# V-00757-00.net
KiCad netlist of a schematic drawn in EAGLE
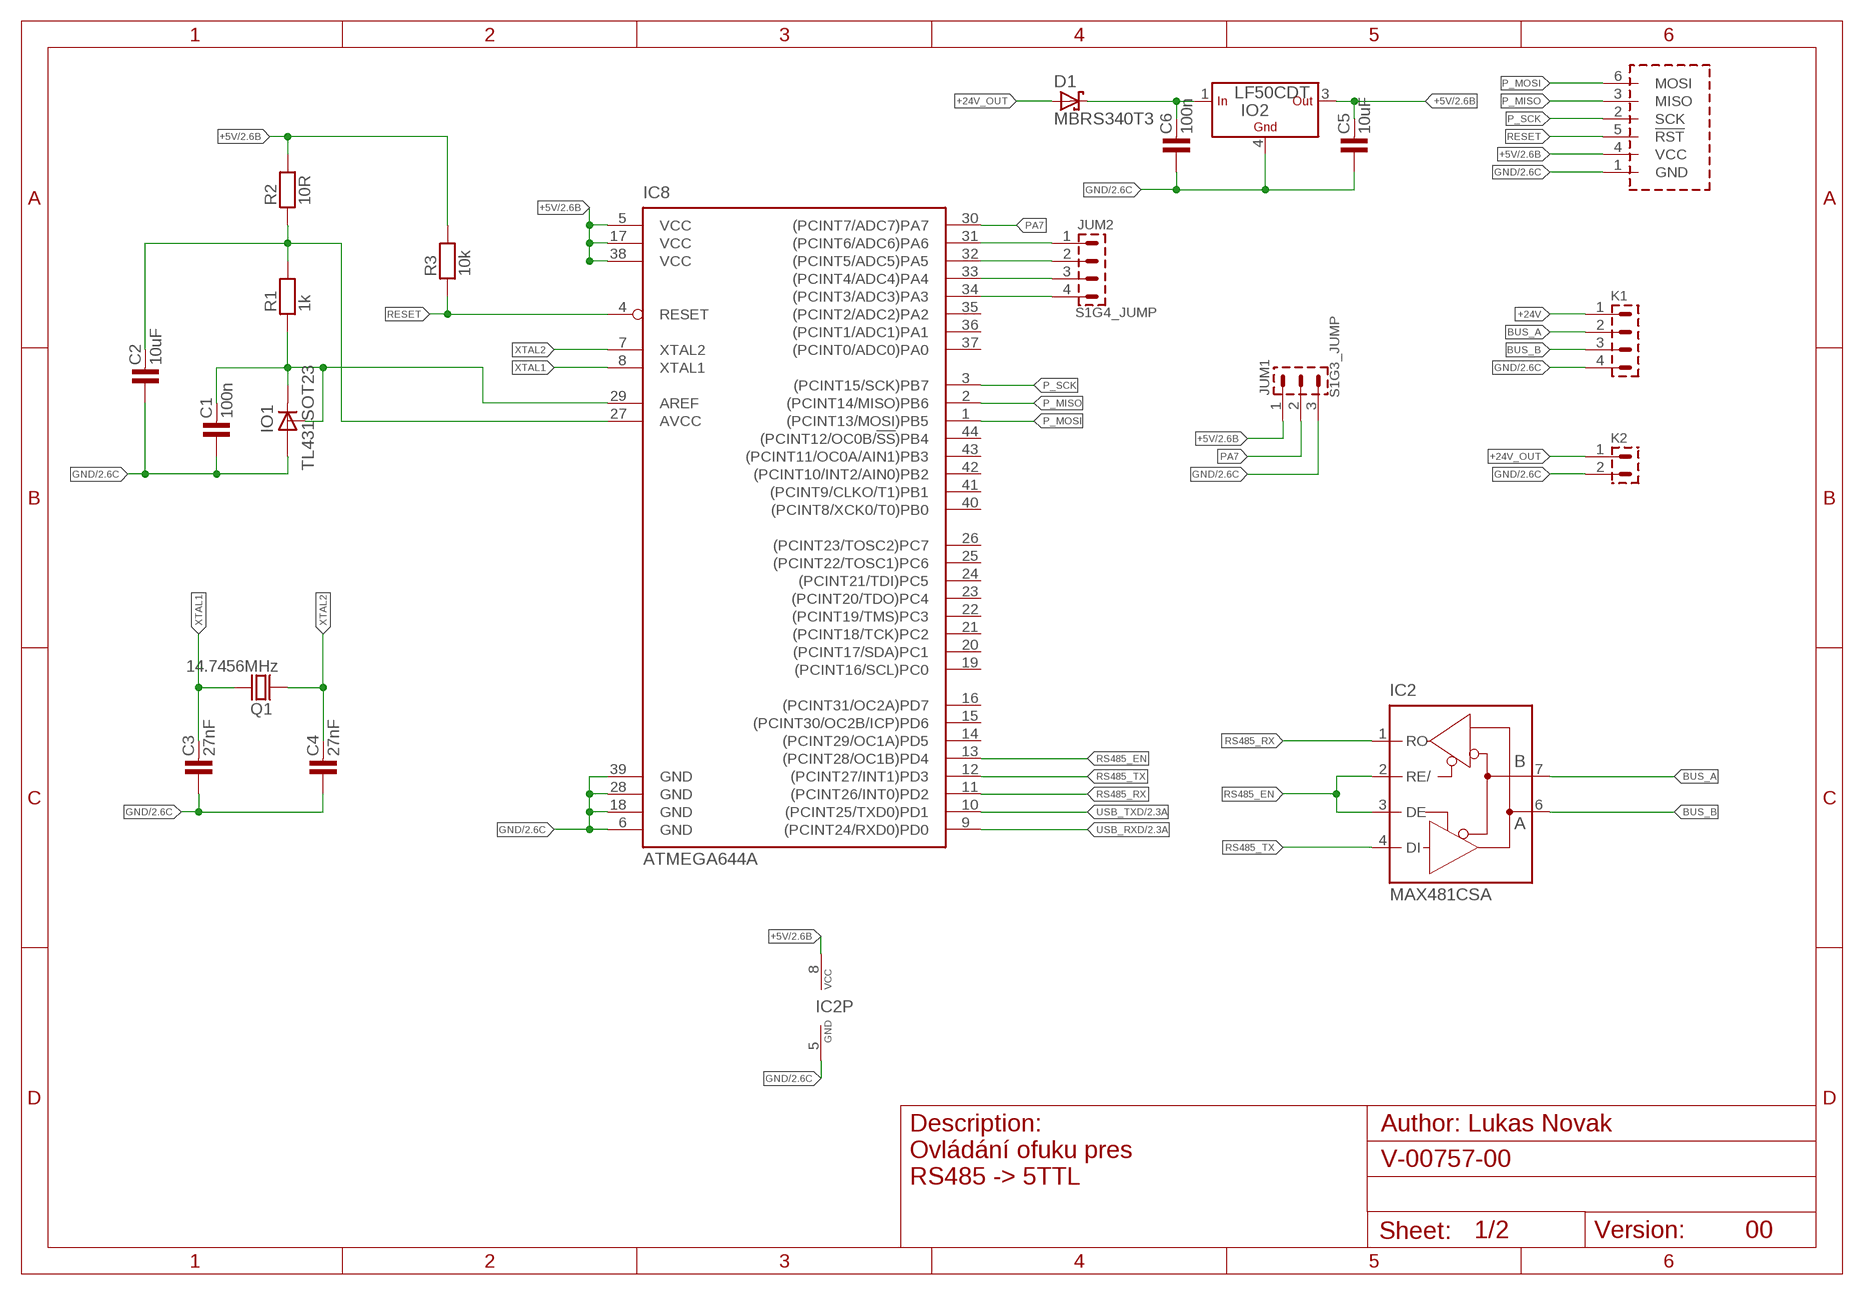
[diagram p0: schematic, sheet 1]
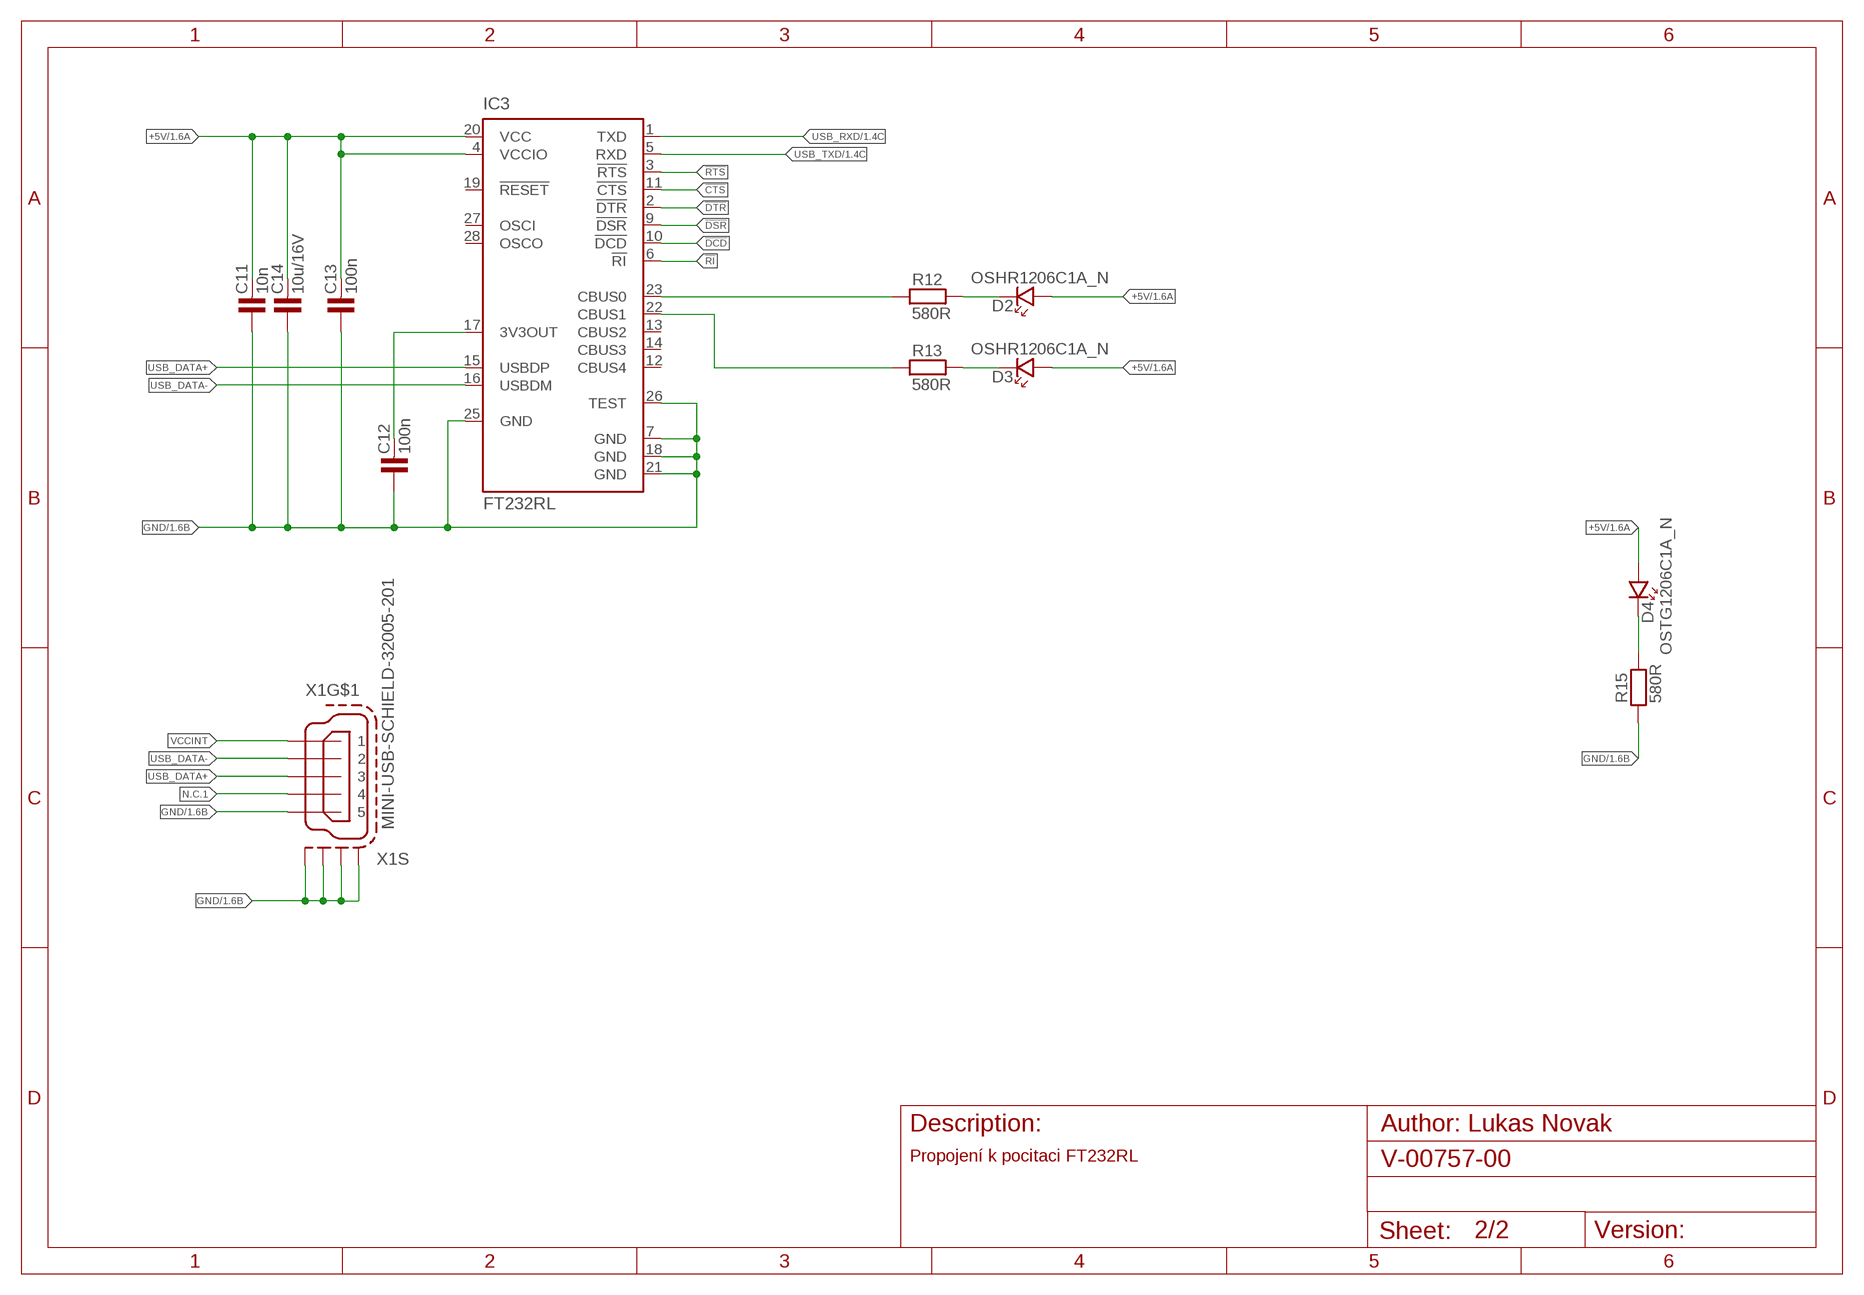
[diagram p1: schematic, sheet 2]

(export (version "E")
  (design (tool "Eeschema 10.0.6"))
  (components
    (comp (ref "C11")
      (value "10n")
      (footprint "eagle-import:1206")
      (libsource (lib "eagle-import") (part "C-KER_1206"))
    )
    (comp (ref "C12")
      (value "100n")
      (footprint "eagle-import:1206")
      (libsource (lib "eagle-import") (part "C-KER_1206"))
    )
    (comp (ref "C13")
      (value "100n")
      (footprint "eagle-import:1206")
      (libsource (lib "eagle-import") (part "C-KER_1206"))
    )
    (comp (ref "C14")
      (value "10u/16V")
      (footprint "eagle-import:1206")
      (libsource (lib "eagle-import") (part "C-KER_1206"))
    )
    (comp (ref "D2")
      (value "OSHR1206C1A_N")
      (footprint "eagle-import:P1206")
      (libsource (lib "eagle-import") (part "LED_1206"))
    )
    (comp (ref "D3")
      (value "OSHR1206C1A_N")
      (footprint "eagle-import:P1206")
      (libsource (lib "eagle-import") (part "LED_1206"))
    )
    (comp (ref "D4")
      (value "OSTG1206C1A_N")
      (footprint "eagle-import:P1206")
      (libsource (lib "eagle-import") (part "LED_1206"))
    )
    (comp (ref "IC3")
      (value "FT232RL")
      (footprint "eagle-import:SSOP28")
      (libsource (lib "eagle-import") (part "FT232RL"))
    )
    (comp (ref "R12")
      (value "580R")
      (footprint "eagle-import:1206")
      (libsource (lib "eagle-import") (part "R_1206"))
    )
    (comp (ref "R13")
      (value "580R")
      (footprint "eagle-import:1206")
      (libsource (lib "eagle-import") (part "R_1206"))
    )
    (comp (ref "R15")
      (value "580R")
      (footprint "eagle-import:1206")
      (libsource (lib "eagle-import") (part "R_1206"))
    )
    (comp (ref "X1")
      (value "MINI-USB-SCHIELD-32005-201")
      (footprint "eagle-import:32005-201")
      (libsource (lib "eagle-import") (part "MINI-USB-SCHIELD-32005-201"))
    )
    (comp (ref "C1")
      (value "100n")
      (footprint "eagle-import:1206")
      (libsource (lib "eagle-import") (part "C-KER_1206"))
    )
    (comp (ref "C2")
      (value "10uF")
      (footprint "eagle-import:1206")
      (libsource (lib "eagle-import") (part "C-KER_1206"))
    )
    (comp (ref "C3")
      (value "27nF")
      (footprint "eagle-import:0805")
      (libsource (lib "eagle-import") (part "C-KER_0805"))
    )
    (comp (ref "C4")
      (value "27nF")
      (footprint "eagle-import:0805")
      (libsource (lib "eagle-import") (part "C-KER_0805"))
    )
    (comp (ref "C5")
      (value "10uF")
      (footprint "eagle-import:1206")
      (libsource (lib "eagle-import") (part "C-KER_1206"))
    )
    (comp (ref "C6")
      (value "100n")
      (footprint "eagle-import:1206")
      (libsource (lib "eagle-import") (part "C-KER_1206"))
    )
    (comp (ref "D1")
      (value "MBRS340T3")
      (footprint "eagle-import:SMC")
      (libsource (lib "eagle-import") (part "MBRS30T34"))
    )
    (comp (ref "IC2")
      (value "MAX481CSA")
      (footprint "eagle-import:SO08")
      (fields (field (name "MF") "MAXIM"))
      (libsource (lib "eagle-import") (part "MAX481CSA"))
    )
    (comp (ref "IC8")
      (value "ATMEGA644A")
      (footprint "eagle-import:TQFP44")
      (fields (field (name "MPN") "ATMEGA644PV-10AU"))
      (libsource (lib "eagle-import") (part "ATMEGA644A"))
    )
    (comp (ref "IO1")
      (value "TL431SOT23")
      (footprint "eagle-import:SOT23")
      (fields (field (name "MPN") "TL431BFDT"))
      (libsource (lib "eagle-import") (part "TL431SOT23"))
    )
    (comp (ref "IO2")
      (value "LF50CDT")
      (footprint "eagle-import:DPAK")
      (libsource (lib "eagle-import") (part "LF_CDT"))
    )
    (comp (ref "JUM1")
      (value "S1G3_JUMP")
      (footprint "eagle-import:S1G3_JUM")
      (libsource (lib "eagle-import") (part "S1G3_JUMP"))
    )
    (comp (ref "JUM2")
      (value "S1G4_JUMP")
      (footprint "eagle-import:S1G4_JUM")
      (libsource (lib "eagle-import") (part "S1G4_JUMP"))
    )
    (comp (ref "K1")
      (value "PSH02-04P")
      (footprint "eagle-import:PSH02-04P")
      (libsource (lib "eagle-import") (part "PSH02-04P"))
    )
    (comp (ref "K2")
      (value "PSH02-02P")
      (footprint "eagle-import:PSH02-02P")
      (libsource (lib "eagle-import") (part "PSH02-02P"))
    )
    (comp (ref "Q1")
      (value "14.7456MHz")
      (footprint "eagle-import:HC-49U")
      (libsource (lib "eagle-import") (part "Q_HC-49U"))
    )
    (comp (ref "R1")
      (value "1k")
      (footprint "eagle-import:1206")
      (libsource (lib "eagle-import") (part "R_1206"))
    )
    (comp (ref "R2")
      (value "10R")
      (footprint "eagle-import:1206")
      (libsource (lib "eagle-import") (part "R_1206"))
    )
    (comp (ref "R3")
      (value "10k")
      (footprint "eagle-import:1206")
      (libsource (lib "eagle-import") (part "R_1206"))
    )
    (comp (ref "U$1")
      (value "AVR_PROG_SPI")
      (footprint "eagle-import:PSH02-06P")
      (libsource (lib "eagle-import") (part "AVR_PROG_SPI"))
    )
  )
  (nets
    (net (code "1") (name "+5V") (class "Default")
      (node (ref "C11") (pin "2") (pinfunction "2_2") (pintype "passive"))
      (node (ref "C13") (pin "2") (pinfunction "2_2") (pintype "passive"))
      (node (ref "C14") (pin "2") (pinfunction "2_2") (pintype "passive"))
      (node (ref "C5") (pin "2") (pinfunction "2_2") (pintype "passive"))
      (node (ref "D2") (pin "A") (pinfunction "A_A") (pintype "passive"))
      (node (ref "D3") (pin "A") (pinfunction "A_A") (pintype "passive"))
      (node (ref "D4") (pin "A") (pinfunction "A_A") (pintype "passive"))
      (node (ref "IC2") (pin "8") (pinfunction "VCC_8") (pintype "power_in"))
      (node (ref "IC3") (pin "20") (pinfunction "VCC_20") (pintype "power_in"))
      (node (ref "IC3") (pin "4") (pinfunction "VCCIO_4") (pintype "power_in"))
      (node (ref "IC8") (pin "17") (pinfunction "VCC_17") (pintype "power_in"))
      (node (ref "IC8") (pin "38") (pinfunction "VCC_38") (pintype "power_in"))
      (node (ref "IC8") (pin "5") (pinfunction "VCC_5") (pintype "power_in"))
      (node (ref "IO2") (pin "3") (pinfunction "OUT_3") (pintype "passive"))
      (node (ref "JUM1") (pin "1") (pinfunction "1_1") (pintype "passive"))
      (node (ref "R2") (pin "2") (pinfunction "2_2") (pintype "passive"))
      (node (ref "R3") (pin "2") (pinfunction "2_2") (pintype "passive"))
      (node (ref "U$1") (pin "4") (pinfunction "VCC_4") (pintype "bidirectional"))
    )
    (net (code "2") (name "+24V") (class "Default")
      (node (ref "C6") (pin "2") (pinfunction "2_2") (pintype "passive"))
      (node (ref "D1") (pin "C") (pinfunction "C_C") (pintype "passive"))
      (node (ref "IO2") (pin "1") (pinfunction "IN_1") (pintype "passive"))
      (node (ref "K1") (pin "1") (pinfunction "1_1") (pintype "passive"))
    )
    (net (code "3") (name "+24V_OUT") (class "Default")
      (node (ref "D1") (pin "A") (pinfunction "A_A") (pintype "passive"))
      (node (ref "K2") (pin "1") (pinfunction "1_1") (pintype "passive"))
    )
    (net (code "4") (name "BUS_A") (class "Default")
      (node (ref "IC2") (pin "7") (pinfunction "B_7") (pintype "passive"))
      (node (ref "K1") (pin "2") (pinfunction "2_2") (pintype "passive"))
    )
    (net (code "5") (name "BUS_B") (class "Default")
      (node (ref "IC2") (pin "6") (pinfunction "A_6") (pintype "passive"))
      (node (ref "K1") (pin "3") (pinfunction "3_3") (pintype "passive"))
    )
    (net (code "6") (name "GND") (class "Default")
      (node (ref "C1") (pin "1") (pinfunction "1_1") (pintype "passive"))
      (node (ref "C11") (pin "1") (pinfunction "1_1") (pintype "passive"))
      (node (ref "C12") (pin "1") (pinfunction "1_1") (pintype "passive"))
      (node (ref "C13") (pin "1") (pinfunction "1_1") (pintype "passive"))
      (node (ref "C14") (pin "1") (pinfunction "1_1") (pintype "passive"))
      (node (ref "C2") (pin "1") (pinfunction "1_1") (pintype "passive"))
      (node (ref "C3") (pin "1") (pinfunction "1_1") (pintype "passive"))
      (node (ref "C4") (pin "1") (pinfunction "1_1") (pintype "passive"))
      (node (ref "C5") (pin "1") (pinfunction "1_1") (pintype "passive"))
      (node (ref "C6") (pin "1") (pinfunction "1_1") (pintype "passive"))
      (node (ref "IC2") (pin "5") (pinfunction "GND_5") (pintype "power_in"))
      (node (ref "IC3") (pin "18") (pinfunction "GND_18") (pintype "power_in"))
      (node (ref "IC3") (pin "21") (pinfunction "GND_21") (pintype "power_in"))
      (node (ref "IC3") (pin "25") (pinfunction "GND_25") (pintype "power_in"))
      (node (ref "IC3") (pin "26") (pinfunction "TEST_26") (pintype "input"))
      (node (ref "IC3") (pin "7") (pinfunction "GND_7") (pintype "power_in"))
      (node (ref "IC8") (pin "18") (pinfunction "GND_18") (pintype "power_in"))
      (node (ref "IC8") (pin "28") (pinfunction "GND_28") (pintype "power_in"))
      (node (ref "IC8") (pin "39") (pinfunction "GND_39") (pintype "power_in"))
      (node (ref "IC8") (pin "6") (pinfunction "GND_6") (pintype "power_in"))
      (node (ref "IO1") (pin "3") (pinfunction "A_3") (pintype "bidirectional"))
      (node (ref "IO2") (pin "4") (pinfunction "GND_4") (pintype "passive"))
      (node (ref "JUM1") (pin "3") (pinfunction "3_3") (pintype "passive"))
      (node (ref "K1") (pin "4") (pinfunction "4_4") (pintype "passive"))
      (node (ref "K2") (pin "2") (pinfunction "2_2") (pintype "passive"))
      (node (ref "R15") (pin "1") (pinfunction "1_1") (pintype "passive"))
      (node (ref "U$1") (pin "1") (pinfunction "GND_1") (pintype "bidirectional"))
      (node (ref "X1") (pin "5") (pinfunction "5_5") (pintype "passive"))
      (node (ref "X1") (pin "M1") (pinfunction "S1_M1") (pintype "passive"))
      (node (ref "X1") (pin "M2") (pinfunction "S2_M2") (pintype "passive"))
      (node (ref "X1") (pin "M3") (pinfunction "S3_M3") (pintype "passive"))
      (node (ref "X1") (pin "M4") (pinfunction "S4_M4") (pintype "passive"))
    )
    (net (code "7") (name "N.C.1") (class "Default")
      (node (ref "X1") (pin "4") (pinfunction "4_4") (pintype "passive"))
    )
    (net (code "8") (name "Net-(D2-PadK)") (class "Default")
      (node (ref "D2") (pin "K") (pinfunction "K_K") (pintype "passive"))
      (node (ref "R12") (pin "2") (pinfunction "2_2") (pintype "passive"))
    )
    (net (code "9") (name "Net-(D3-PadK)") (class "Default")
      (node (ref "D3") (pin "K") (pinfunction "K_K") (pintype "passive"))
      (node (ref "R13") (pin "2") (pinfunction "2_2") (pintype "passive"))
    )
    (net (code "10") (name "Net-(D4-PadK)") (class "Default")
      (node (ref "D4") (pin "K") (pinfunction "K_K") (pintype "passive"))
      (node (ref "R15") (pin "2") (pinfunction "2_2") (pintype "passive"))
    )
    (net (code "11") (name "Net-(IC3-3V3OUT)") (class "Default")
      (node (ref "C12") (pin "2") (pinfunction "2_2") (pintype "passive"))
      (node (ref "IC3") (pin "17") (pinfunction "3V3OUT_17") (pintype "output"))
    )
    (net (code "12") (name "Net-(IC3-CBUS0)") (class "Default")
      (node (ref "IC3") (pin "23") (pinfunction "CBUS0_23") (pintype "bidirectional"))
      (node (ref "R12") (pin "1") (pinfunction "1_1") (pintype "passive"))
    )
    (net (code "13") (name "Net-(IC3-CBUS1)") (class "Default")
      (node (ref "IC3") (pin "22") (pinfunction "CBUS1_22") (pintype "bidirectional"))
      (node (ref "R13") (pin "1") (pinfunction "1_1") (pintype "passive"))
    )
    (net (code "14") (name "Net-(IC8-(PCINT3{slash}ADC3)PA3)") (class "Default")
      (node (ref "IC8") (pin "34") (pinfunction "(PCINT3/ADC3)PA3_34") (pintype "bidirectional"))
      (node (ref "JUM2") (pin "4") (pinfunction "4_4") (pintype "passive"))
    )
    (net (code "15") (name "Net-(IC8-(PCINT4{slash}ADC4)PA4)") (class "Default")
      (node (ref "IC8") (pin "33") (pinfunction "(PCINT4/ADC4)PA4_33") (pintype "bidirectional"))
      (node (ref "JUM2") (pin "3") (pinfunction "3_3") (pintype "passive"))
    )
    (net (code "16") (name "Net-(IC8-(PCINT5{slash}ADC5)PA5)") (class "Default")
      (node (ref "IC8") (pin "32") (pinfunction "(PCINT5/ADC5)PA5_32") (pintype "bidirectional"))
      (node (ref "JUM2") (pin "2") (pinfunction "2_2") (pintype "passive"))
    )
    (net (code "17") (name "Net-(IC8-(PCINT6{slash}ADC6)PA6)") (class "Default")
      (node (ref "IC8") (pin "31") (pinfunction "(PCINT6/ADC6)PA6_31") (pintype "bidirectional"))
      (node (ref "JUM2") (pin "1") (pinfunction "1_1") (pintype "passive"))
    )
    (net (code "18") (name "Net-(IC8-AREF)") (class "Default")
      (node (ref "C1") (pin "2") (pinfunction "2_2") (pintype "passive"))
      (node (ref "IC8") (pin "29") (pinfunction "AREF_29") (pintype "passive"))
      (node (ref "IO1") (pin "1") (pinfunction "C_1") (pintype "bidirectional"))
      (node (ref "IO1") (pin "2") (pinfunction "R_2") (pintype "bidirectional"))
      (node (ref "R1") (pin "1") (pinfunction "1_1") (pintype "passive"))
    )
    (net (code "19") (name "Net-(IC8-AVCC)") (class "Default")
      (node (ref "C2") (pin "2") (pinfunction "2_2") (pintype "passive"))
      (node (ref "IC8") (pin "27") (pinfunction "AVCC_27") (pintype "power_in"))
      (node (ref "R1") (pin "2") (pinfunction "2_2") (pintype "passive"))
      (node (ref "R2") (pin "1") (pinfunction "1_1") (pintype "passive"))
    )
    (net (code "20") (name "PA7") (class "Default")
      (node (ref "IC8") (pin "30") (pinfunction "(PCINT7/ADC7)PA7_30") (pintype "bidirectional"))
      (node (ref "JUM1") (pin "2") (pinfunction "2_2") (pintype "passive"))
    )
    (net (code "21") (name "P_MISO") (class "Default")
      (node (ref "IC8") (pin "2") (pinfunction "(PCINT14/MISO)PB6_2") (pintype "bidirectional"))
      (node (ref "U$1") (pin "3") (pinfunction "MISO_3") (pintype "bidirectional"))
    )
    (net (code "22") (name "P_MOSI") (class "Default")
      (node (ref "IC8") (pin "1") (pinfunction "(PCINT13/MOSI)PB5_1") (pintype "bidirectional"))
      (node (ref "U$1") (pin "6") (pinfunction "MOSI_6") (pintype "bidirectional"))
    )
    (net (code "23") (name "P_SCK") (class "Default")
      (node (ref "IC8") (pin "3") (pinfunction "(PCINT15/SCK)PB7_3") (pintype "bidirectional"))
      (node (ref "U$1") (pin "2") (pinfunction "SCK_2") (pintype "bidirectional"))
    )
    (net (code "24") (name "RESET") (class "Default")
      (node (ref "IC8") (pin "4") (pinfunction "RESET_4") (pintype "input"))
      (node (ref "R3") (pin "1") (pinfunction "1_1") (pintype "passive"))
      (node (ref "U$1") (pin "5") (pinfunction "~{RST}_5") (pintype "bidirectional"))
    )
    (net (code "25") (name "RS485_EN") (class "Default")
      (node (ref "IC2") (pin "2") (pinfunction "RE/_2") (pintype "input"))
      (node (ref "IC2") (pin "3") (pinfunction "DE_3") (pintype "input"))
      (node (ref "IC8") (pin "13") (pinfunction "(PCINT28/OC1B)PD4_13") (pintype "bidirectional"))
    )
    (net (code "26") (name "RS485_RX") (class "Default")
      (node (ref "IC2") (pin "1") (pinfunction "RO_1") (pintype "output"))
      (node (ref "IC8") (pin "11") (pinfunction "(PCINT26/INT0)PD2_11") (pintype "bidirectional"))
    )
    (net (code "27") (name "RS485_TX") (class "Default")
      (node (ref "IC2") (pin "4") (pinfunction "DI_4") (pintype "input"))
      (node (ref "IC8") (pin "12") (pinfunction "(PCINT27/INT1)PD3_12") (pintype "bidirectional"))
    )
    (net (code "28") (name "USB_DATA+") (class "Default")
      (node (ref "IC3") (pin "15") (pinfunction "USBDP_15") (pintype "bidirectional"))
      (node (ref "X1") (pin "3") (pinfunction "3_3") (pintype "passive"))
    )
    (net (code "29") (name "USB_DATA-") (class "Default")
      (node (ref "IC3") (pin "16") (pinfunction "USBDM_16") (pintype "bidirectional"))
      (node (ref "X1") (pin "2") (pinfunction "2_2") (pintype "passive"))
    )
    (net (code "30") (name "USB_RXD") (class "Default")
      (node (ref "IC3") (pin "1") (pinfunction "TXD_1") (pintype "output"))
      (node (ref "IC8") (pin "9") (pinfunction "(PCINT24/RXD0)PD0_9") (pintype "bidirectional"))
    )
    (net (code "31") (name "USB_TXD") (class "Default")
      (node (ref "IC3") (pin "5") (pinfunction "RXD_5") (pintype "input"))
      (node (ref "IC8") (pin "10") (pinfunction "(PCINT25/TXD0)PD1_10") (pintype "bidirectional"))
    )
    (net (code "32") (name "VCCINT") (class "Default")
      (node (ref "X1") (pin "1") (pinfunction "1_1") (pintype "passive"))
    )
    (net (code "33") (name "XTAL1") (class "Default")
      (node (ref "C3") (pin "2") (pinfunction "2_2") (pintype "passive"))
      (node (ref "IC8") (pin "8") (pinfunction "XTAL1_8") (pintype "bidirectional"))
      (node (ref "Q1") (pin "2") (pinfunction "2_2") (pintype "passive"))
    )
    (net (code "34") (name "XTAL2") (class "Default")
      (node (ref "C4") (pin "2") (pinfunction "2_2") (pintype "passive"))
      (node (ref "IC8") (pin "7") (pinfunction "XTAL2_7") (pintype "bidirectional"))
      (node (ref "Q1") (pin "1") (pinfunction "1_1") (pintype "passive"))
    )
    (net (code "35") (name "unconnected-(IC3-CBUS2-Pad13)") (class "Default")
      (node (ref "IC3") (pin "13") (pinfunction "CBUS2_13") (pintype "bidirectional"))
    )
    (net (code "36") (name "unconnected-(IC3-CBUS3-Pad14)") (class "Default")
      (node (ref "IC3") (pin "14") (pinfunction "CBUS3_14") (pintype "bidirectional"))
    )
    (net (code "37") (name "unconnected-(IC3-CBUS4-Pad12)") (class "Default")
      (node (ref "IC3") (pin "12") (pinfunction "CBUS4_12") (pintype "bidirectional"))
    )
    (net (code "38") (name "unconnected-(IC3-OSCI-Pad27)") (class "Default")
      (node (ref "IC3") (pin "27") (pinfunction "OSCI_27") (pintype "input"))
    )
    (net (code "39") (name "unconnected-(IC3-OSCO-Pad28)") (class "Default")
      (node (ref "IC3") (pin "28") (pinfunction "OSCO_28") (pintype "output"))
    )
    (net (code "40") (name "unconnected-(IC3-~{RESET}-Pad19)") (class "Default")
      (node (ref "IC3") (pin "19") (pinfunction "~{RESET}_19") (pintype "input"))
    )
    (net (code "41") (name "unconnected-(IC8-(PCINT0{slash}ADC0)PA0-Pad37)") (class "Default")
      (node (ref "IC8") (pin "37") (pinfunction "(PCINT0/ADC0)PA0_37") (pintype "bidirectional"))
    )
    (net (code "42") (name "unconnected-(IC8-(PCINT1{slash}ADC1)PA1-Pad36)") (class "Default")
      (node (ref "IC8") (pin "36") (pinfunction "(PCINT1/ADC1)PA1_36") (pintype "bidirectional"))
    )
    (net (code "43") (name "unconnected-(IC8-(PCINT2{slash}ADC2)PA2-Pad35)") (class "Default")
      (node (ref "IC8") (pin "35") (pinfunction "(PCINT2/ADC2)PA2_35") (pintype "bidirectional"))
    )
    (net (code "44") (name "unconnected-(IC8-(PCINT8{slash}XCK0{slash}T0)PB0-Pad40)") (class "Default")
      (node (ref "IC8") (pin "40") (pinfunction "(PCINT8/XCK0/T0)PB0_40") (pintype "bidirectional"))
    )
    (net (code "45") (name "unconnected-(IC8-(PCINT9{slash}CLKO{slash}T1)PB1-Pad41)") (class "Default")
      (node (ref "IC8") (pin "41") (pinfunction "(PCINT9/CLKO/T1)PB1_41") (pintype "bidirectional"))
    )
    (net (code "46") (name "unconnected-(IC8-(PCINT10{slash}INT2{slash}AIN0)PB2-Pad42)") (class "Default")
      (node (ref "IC8") (pin "42") (pinfunction "(PCINT10/INT2/AIN0)PB2_42") (pintype "bidirectional"))
    )
    (net (code "47") (name "unconnected-(IC8-(PCINT11{slash}OC0A{slash}AIN1)PB3-Pad43)") (class "Default")
      (node (ref "IC8") (pin "43") (pinfunction "(PCINT11/OC0A/AIN1)PB3_43") (pintype "bidirectional"))
    )
    (net (code "48") (name "unconnected-(IC8-(PCINT12{slash}OC0B{slash}~{SS})PB4-Pad44)") (class "Default")
      (node (ref "IC8") (pin "44") (pinfunction "(PCINT12/OC0B/~{SS})PB4_44") (pintype "bidirectional"))
    )
    (net (code "49") (name "unconnected-(IC8-(PCINT16{slash}SCL)PC0-Pad19)") (class "Default")
      (node (ref "IC8") (pin "19") (pinfunction "(PCINT16/SCL)PC0_19") (pintype "output"))
    )
    (net (code "50") (name "unconnected-(IC8-(PCINT17{slash}SDA)PC1-Pad20)") (class "Default")
      (node (ref "IC8") (pin "20") (pinfunction "(PCINT17/SDA)PC1_20") (pintype "output"))
    )
    (net (code "51") (name "unconnected-(IC8-(PCINT18{slash}TCK)PC2-Pad21)") (class "Default")
      (node (ref "IC8") (pin "21") (pinfunction "(PCINT18/TCK)PC2_21") (pintype "output"))
    )
    (net (code "52") (name "unconnected-(IC8-(PCINT19{slash}TMS)PC3-Pad22)") (class "Default")
      (node (ref "IC8") (pin "22") (pinfunction "(PCINT19/TMS)PC3_22") (pintype "output"))
    )
    (net (code "53") (name "unconnected-(IC8-(PCINT20{slash}TDO)PC4-Pad23)") (class "Default")
      (node (ref "IC8") (pin "23") (pinfunction "(PCINT20/TDO)PC4_23") (pintype "output"))
    )
    (net (code "54") (name "unconnected-(IC8-(PCINT21{slash}TDI)PC5-Pad24)") (class "Default")
      (node (ref "IC8") (pin "24") (pinfunction "(PCINT21/TDI)PC5_24") (pintype "output"))
    )
    (net (code "55") (name "unconnected-(IC8-(PCINT22{slash}TOSC1)PC6-Pad25)") (class "Default")
      (node (ref "IC8") (pin "25") (pinfunction "(PCINT22/TOSC1)PC6_25") (pintype "output"))
    )
    (net (code "56") (name "unconnected-(IC8-(PCINT23{slash}TOSC2)PC7-Pad26)") (class "Default")
      (node (ref "IC8") (pin "26") (pinfunction "(PCINT23/TOSC2)PC7_26") (pintype "output"))
    )
    (net (code "57") (name "unconnected-(IC8-(PCINT29{slash}OC1A)PD5-Pad14)") (class "Default")
      (node (ref "IC8") (pin "14") (pinfunction "(PCINT29/OC1A)PD5_14") (pintype "bidirectional"))
    )
    (net (code "58") (name "unconnected-(IC8-(PCINT30{slash}OC2B{slash}ICP)PD6-Pad15)") (class "Default")
      (node (ref "IC8") (pin "15") (pinfunction "(PCINT30/OC2B/ICP)PD6_15") (pintype "bidirectional"))
    )
    (net (code "59") (name "unconnected-(IC8-(PCINT31{slash}OC2A)PD7-Pad16)") (class "Default")
      (node (ref "IC8") (pin "16") (pinfunction "(PCINT31/OC2A)PD7_16") (pintype "bidirectional"))
    )
    (net (code "60") (name "~{CTS}") (class "Default")
      (node (ref "IC3") (pin "11") (pinfunction "~{CTS}_11") (pintype "input"))
    )
    (net (code "61") (name "~{DCD}") (class "Default")
      (node (ref "IC3") (pin "10") (pinfunction "~{DCD}_10") (pintype "input"))
    )
    (net (code "62") (name "~{DSR}") (class "Default")
      (node (ref "IC3") (pin "9") (pinfunction "~{DSR}_9") (pintype "input"))
    )
    (net (code "63") (name "~{DTR}") (class "Default")
      (node (ref "IC3") (pin "2") (pinfunction "~{DTR}_2") (pintype "output"))
    )
    (net (code "64") (name "~{RI}") (class "Default")
      (node (ref "IC3") (pin "6") (pinfunction "~{RI}_6") (pintype "input"))
    )
    (net (code "65") (name "~{RTS}") (class "Default")
      (node (ref "IC3") (pin "3") (pinfunction "~{RTS}_3") (pintype "output"))
    )
  )
)
